# atas.net
KiCad netlist of a schematic drawn in EAGLE
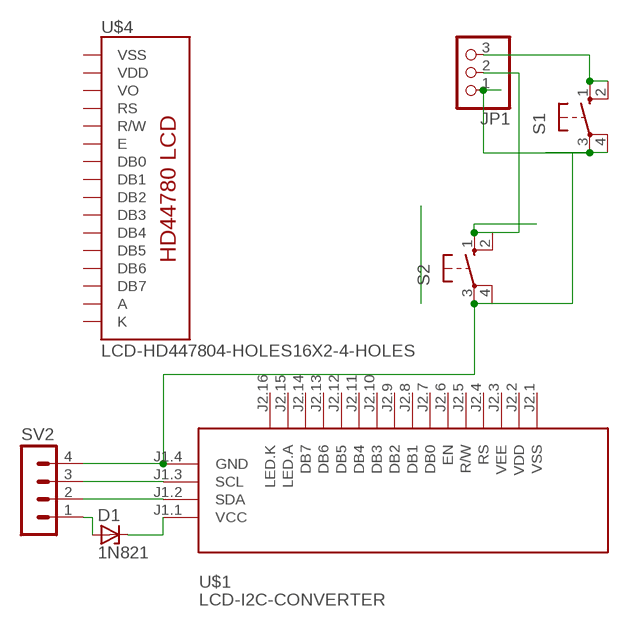
[diagram p0: schematic, sheet 1]

(export (version "E")
  (design (tool "Eeschema 10.0.6"))
  (components
    (comp (ref "D1")
      (value "1N821")
      (footprint "eagle-import:DO35Z10")
      (libsource (lib "eagle-import") (part "1N821"))
    )
    (comp (ref "JP1")
      (value "PINHD-1X3/90")
      (footprint "eagle-import:1X03_90")
      (libsource (lib "eagle-import") (part "PINHD-1X3/90"))
    )
    (comp (ref "S1")
      (value "10-XX")
      (footprint "eagle-import:B3F-10XX")
      (fields (field (name "MPN") "B3F-1000"))
      (libsource (lib "eagle-import") (part "10-XX"))
    )
    (comp (ref "S2")
      (value "10-XX")
      (footprint "eagle-import:B3F-10XX")
      (fields (field (name "MPN") "B3F-1000"))
      (libsource (lib "eagle-import") (part "10-XX"))
    )
    (comp (ref "SV2")
      (value "MA04-1")
      (footprint "eagle-import:MA04-1")
      (libsource (lib "eagle-import") (part "MA04-1"))
    )
    (comp (ref "U$1")
      (value "LCD-I2C-CONVERTER")
      (footprint "eagle-import:LCD-I2C-CONVERTER")
      (libsource (lib "eagle-import") (part "LCD-I2C-CONVERTER"))
    )
    (comp (ref "U$4")
      (value "LCD-HD447804-HOLES16X2-4-HOLES")
      (footprint "eagle-import:LCD-16X2-4HOLES")
      (libsource (lib "eagle-import") (part "LCD-HD4478016X2-4-HOLES4-HOLES"))
    )
  )
  (nets
    (net (code "1") (name "/A") (class "Default")
      (node (ref "U$4") (pin "15") (pinfunction "A_15") (pintype "power_in"))
    )
    (net (code "2") (name "/K") (class "Default")
      (node (ref "U$4") (pin "16") (pinfunction "K_16") (pintype "power_in"))
    )
    (net (code "3") (name "/VDD") (class "Default")
      (node (ref "U$4") (pin "2") (pinfunction "VDD_2") (pintype "power_in"))
    )
    (net (code "4") (name "/VSS") (class "Default")
      (node (ref "U$4") (pin "1") (pinfunction "VSS_1") (pintype "power_in"))
    )
    (net (code "5") (name "Net-(D1-PadA)") (class "Default")
      (node (ref "D1") (pin "A") (pinfunction "A_A") (pintype "passive"))
      (node (ref "SV2") (pin "1") (pinfunction "1_1") (pintype "passive"))
    )
    (net (code "6") (name "Net-(S1-P)") (class "Default")
      (node (ref "JP1") (pin "1") (pinfunction "1_1") (pintype "passive"))
      (node (ref "S1") (pin "3") (pinfunction "P_3") (pintype "passive"))
      (node (ref "S1") (pin "4") (pinfunction "P1_4") (pintype "passive"))
      (node (ref "S2") (pin "3") (pinfunction "P_3") (pintype "passive"))
      (node (ref "S2") (pin "4") (pinfunction "P1_4") (pintype "passive"))
      (node (ref "SV2") (pin "4") (pinfunction "4_4") (pintype "passive"))
      (node (ref "U$1") (pin "J1.4") (pinfunction "GND_J1.4") (pintype "power_in"))
    )
    (net (code "7") (name "Net-(S1-S)") (class "Default")
      (node (ref "JP1") (pin "3") (pinfunction "3_3") (pintype "passive"))
      (node (ref "S1") (pin "1") (pinfunction "S_1") (pintype "passive"))
      (node (ref "S1") (pin "2") (pinfunction "S1_2") (pintype "passive"))
    )
    (net (code "8") (name "Net-(S2-S)") (class "Default")
      (node (ref "JP1") (pin "2") (pinfunction "2_2") (pintype "passive"))
      (node (ref "S2") (pin "1") (pinfunction "S_1") (pintype "passive"))
      (node (ref "S2") (pin "2") (pinfunction "S1_2") (pintype "passive"))
    )
    (net (code "9") (name "Net-(U$1-SCL)") (class "Default")
      (node (ref "SV2") (pin "3") (pinfunction "3_3") (pintype "passive"))
      (node (ref "U$1") (pin "J1.3") (pinfunction "SCL_J1.3") (pintype "bidirectional"))
    )
    (net (code "10") (name "Net-(U$1-SDA)") (class "Default")
      (node (ref "SV2") (pin "2") (pinfunction "2_2") (pintype "passive"))
      (node (ref "U$1") (pin "J1.2") (pinfunction "SDA_J1.2") (pintype "bidirectional"))
    )
    (net (code "11") (name "Net-(U$1-VCC)") (class "Default")
      (node (ref "D1") (pin "C") (pinfunction "C_C") (pintype "passive"))
      (node (ref "U$1") (pin "J1.1") (pinfunction "VCC_J1.1") (pintype "power_in"))
    )
    (net (code "12") (name "unconnected-(U$1-DB0-PadJ2.7)") (class "Default")
      (node (ref "U$1") (pin "J2.7") (pinfunction "DB0_J2.7") (pintype "bidirectional"))
    )
    (net (code "13") (name "unconnected-(U$1-DB1-PadJ2.8)") (class "Default")
      (node (ref "U$1") (pin "J2.8") (pinfunction "DB1_J2.8") (pintype "bidirectional"))
    )
    (net (code "14") (name "unconnected-(U$1-DB2-PadJ2.9)") (class "Default")
      (node (ref "U$1") (pin "J2.9") (pinfunction "DB2_J2.9") (pintype "bidirectional"))
    )
    (net (code "15") (name "unconnected-(U$1-DB3-PadJ2.10)") (class "Default")
      (node (ref "U$1") (pin "J2.10") (pinfunction "DB3_J2.10") (pintype "bidirectional"))
    )
    (net (code "16") (name "unconnected-(U$1-DB4-PadJ2.11)") (class "Default")
      (node (ref "U$1") (pin "J2.11") (pinfunction "DB4_J2.11") (pintype "bidirectional"))
    )
    (net (code "17") (name "unconnected-(U$1-DB5-PadJ2.12)") (class "Default")
      (node (ref "U$1") (pin "J2.12") (pinfunction "DB5_J2.12") (pintype "bidirectional"))
    )
    (net (code "18") (name "unconnected-(U$1-DB6-PadJ2.13)") (class "Default")
      (node (ref "U$1") (pin "J2.13") (pinfunction "DB6_J2.13") (pintype "bidirectional"))
    )
    (net (code "19") (name "unconnected-(U$1-DB7-PadJ2.14)") (class "Default")
      (node (ref "U$1") (pin "J2.14") (pinfunction "DB7_J2.14") (pintype "bidirectional"))
    )
    (net (code "20") (name "unconnected-(U$1-EN-PadJ2.6)") (class "Default")
      (node (ref "U$1") (pin "J2.6") (pinfunction "EN_J2.6") (pintype "bidirectional"))
    )
    (net (code "21") (name "unconnected-(U$1-LED.A-PadJ2.15)") (class "Default")
      (node (ref "U$1") (pin "J2.15") (pinfunction "LED.A_J2.15") (pintype "bidirectional"))
    )
    (net (code "22") (name "unconnected-(U$1-LED.K-PadJ2.16)") (class "Default")
      (node (ref "U$1") (pin "J2.16") (pinfunction "LED.K_J2.16") (pintype "bidirectional"))
    )
    (net (code "23") (name "unconnected-(U$1-RS-PadJ2.4)") (class "Default")
      (node (ref "U$1") (pin "J2.4") (pinfunction "RS_J2.4") (pintype "bidirectional"))
    )
    (net (code "24") (name "unconnected-(U$1-R{slash}W-PadJ2.5)") (class "Default")
      (node (ref "U$1") (pin "J2.5") (pinfunction "R/W_J2.5") (pintype "bidirectional"))
    )
    (net (code "25") (name "unconnected-(U$1-VDD-PadJ2.2)") (class "Default")
      (node (ref "U$1") (pin "J2.2") (pinfunction "VDD_J2.2") (pintype "bidirectional"))
    )
    (net (code "26") (name "unconnected-(U$1-VEE-PadJ2.3)") (class "Default")
      (node (ref "U$1") (pin "J2.3") (pinfunction "VEE_J2.3") (pintype "bidirectional"))
    )
    (net (code "27") (name "unconnected-(U$1-VSS-PadJ2.1)") (class "Default")
      (node (ref "U$1") (pin "J2.1") (pinfunction "VSS_J2.1") (pintype "bidirectional"))
    )
    (net (code "28") (name "unconnected-(U$4-DB0-Pad7)") (class "Default")
      (node (ref "U$4") (pin "7") (pinfunction "DB0_7") (pintype "bidirectional"))
    )
    (net (code "29") (name "unconnected-(U$4-DB1-Pad8)") (class "Default")
      (node (ref "U$4") (pin "8") (pinfunction "DB1_8") (pintype "bidirectional"))
    )
    (net (code "30") (name "unconnected-(U$4-DB2-Pad9)") (class "Default")
      (node (ref "U$4") (pin "9") (pinfunction "DB2_9") (pintype "bidirectional"))
    )
    (net (code "31") (name "unconnected-(U$4-DB3-Pad10)") (class "Default")
      (node (ref "U$4") (pin "10") (pinfunction "DB3_10") (pintype "bidirectional"))
    )
    (net (code "32") (name "unconnected-(U$4-DB4-Pad11)") (class "Default")
      (node (ref "U$4") (pin "11") (pinfunction "DB4_11") (pintype "bidirectional"))
    )
    (net (code "33") (name "unconnected-(U$4-DB5-Pad12)") (class "Default")
      (node (ref "U$4") (pin "12") (pinfunction "DB5_12") (pintype "bidirectional"))
    )
    (net (code "34") (name "unconnected-(U$4-DB6-Pad13)") (class "Default")
      (node (ref "U$4") (pin "13") (pinfunction "DB6_13") (pintype "bidirectional"))
    )
    (net (code "35") (name "unconnected-(U$4-DB7-Pad14)") (class "Default")
      (node (ref "U$4") (pin "14") (pinfunction "DB7_14") (pintype "bidirectional"))
    )
    (net (code "36") (name "unconnected-(U$4-E-Pad6)") (class "Default")
      (node (ref "U$4") (pin "6") (pinfunction "E_6") (pintype "input"))
    )
    (net (code "37") (name "unconnected-(U$4-RS-Pad4)") (class "Default")
      (node (ref "U$4") (pin "4") (pinfunction "RS_4") (pintype "input"))
    )
    (net (code "38") (name "unconnected-(U$4-R{slash}W-Pad5)") (class "Default")
      (node (ref "U$4") (pin "5") (pinfunction "R/W_5") (pintype "input"))
    )
    (net (code "39") (name "unconnected-(U$4-VO-Pad3)") (class "Default")
      (node (ref "U$4") (pin "3") (pinfunction "VO_3") (pintype "bidirectional"))
    )
  )
)
